# xclock_B.net
KiCad netlist of a schematic drawn in EAGLE
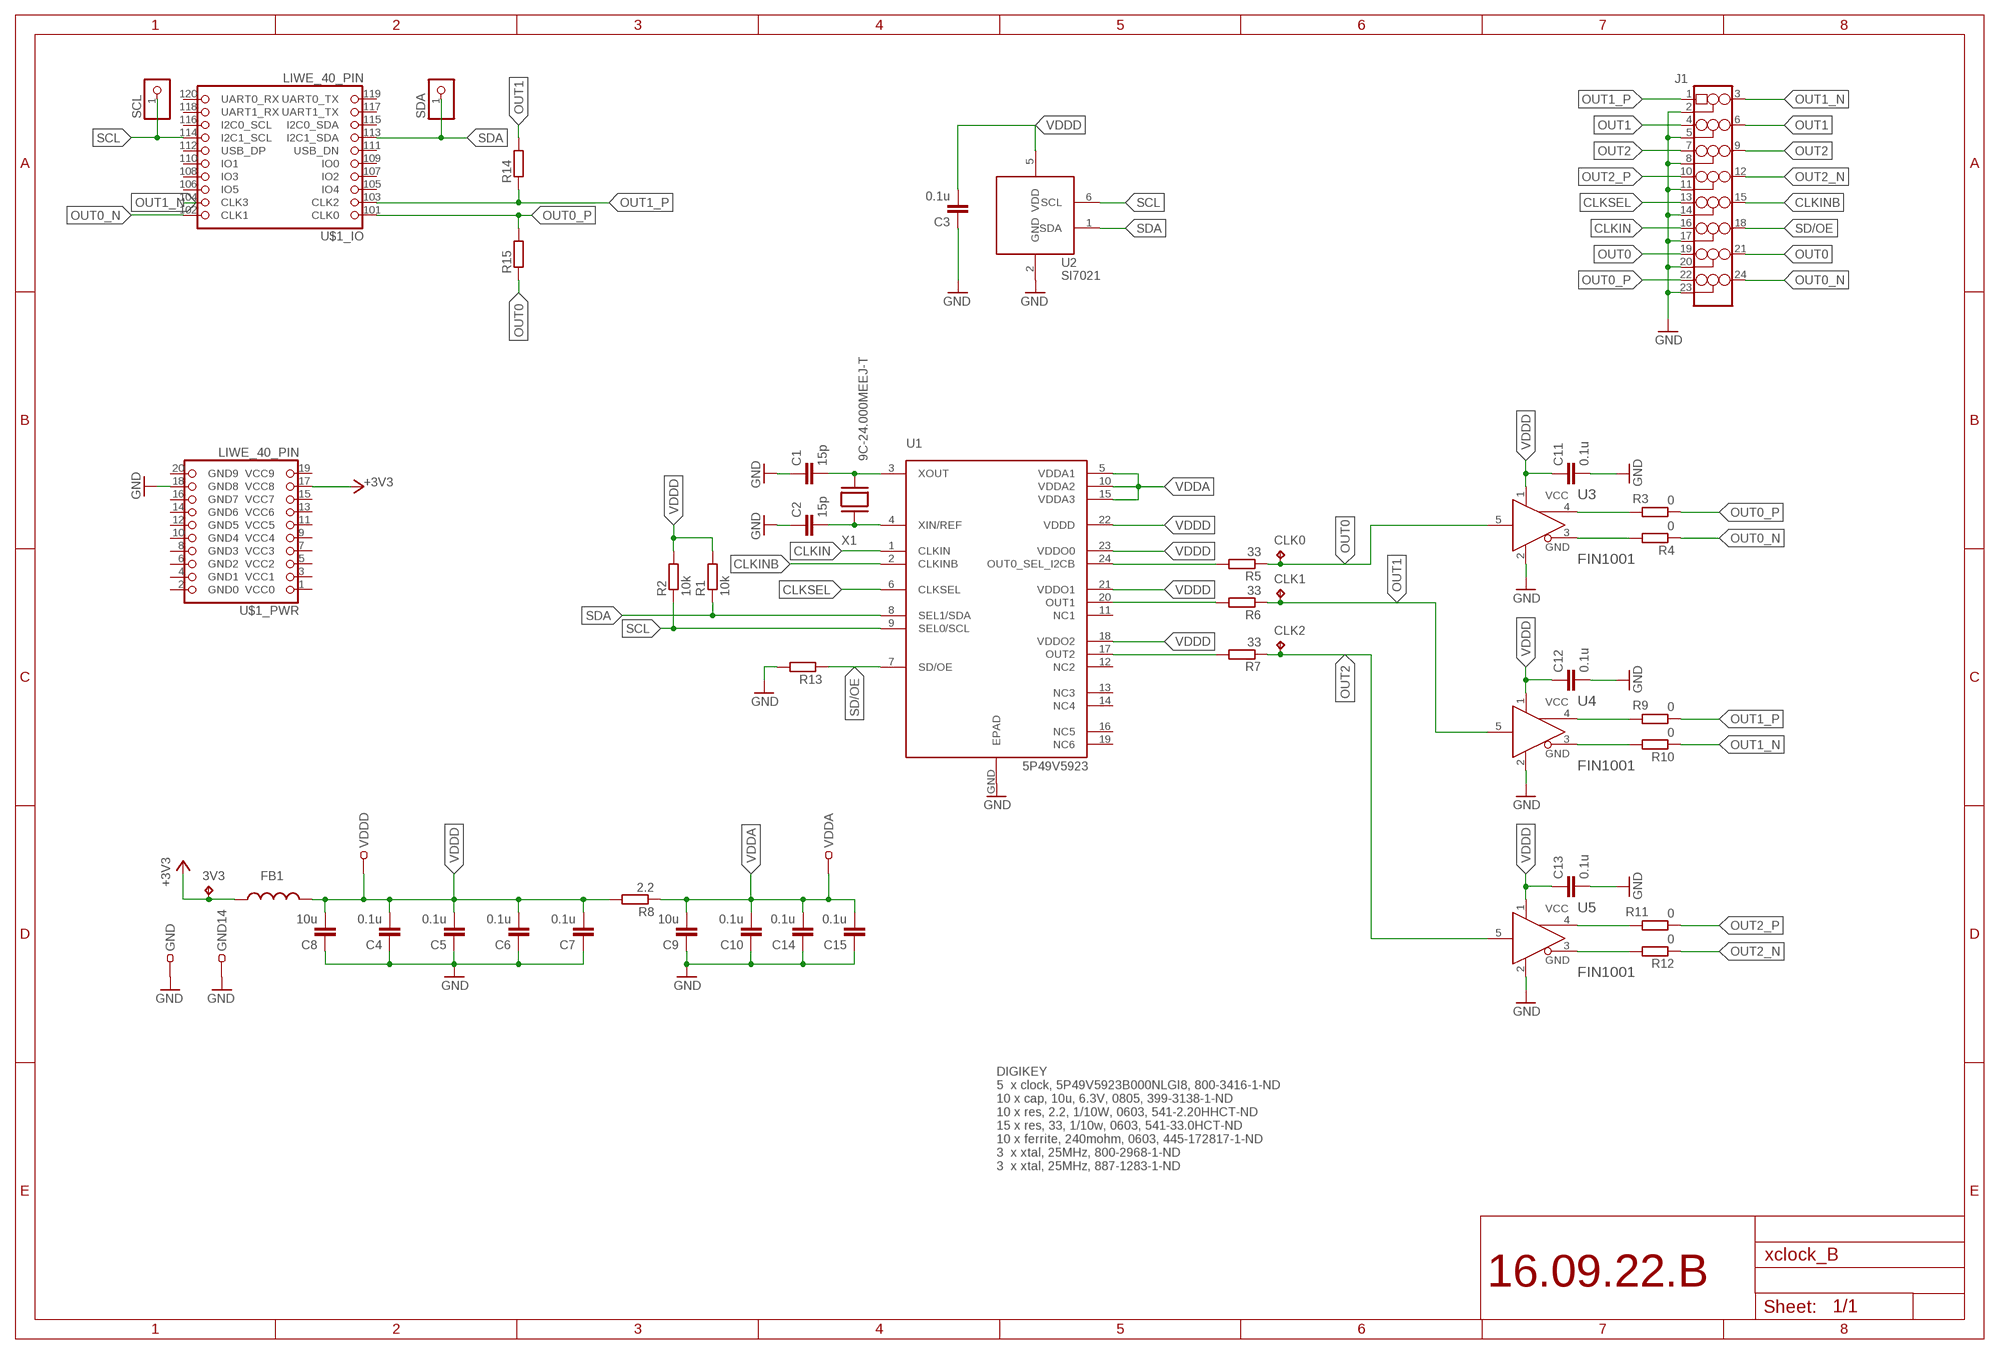
[diagram p0: schematic, sheet 1]

(export (version "E")
  (design (tool "Eeschema 10.0.6"))
  (components
    (comp (ref "3V3")
      (value "TPB1,27")
      (footprint "eagle-import:B1,27")
      (libsource (lib "eagle-import") (part "TPB1,27"))
    )
    (comp (ref "C1")
      (value "15p")
      (footprint "eagle-import:C0603")
      (libsource (lib "eagle-import") (part "C-EUC0603"))
    )
    (comp (ref "C2")
      (value "15p")
      (footprint "eagle-import:C0603")
      (libsource (lib "eagle-import") (part "C-EUC0603"))
    )
    (comp (ref "C3")
      (value "0.1u")
      (footprint "eagle-import:C0603")
      (libsource (lib "eagle-import") (part "C-EUC0603"))
    )
    (comp (ref "C4")
      (value "0.1u")
      (footprint "eagle-import:C0603")
      (libsource (lib "eagle-import") (part "C-EUC0603"))
    )
    (comp (ref "C5")
      (value "0.1u")
      (footprint "eagle-import:C0603")
      (libsource (lib "eagle-import") (part "C-EUC0603"))
    )
    (comp (ref "C6")
      (value "0.1u")
      (footprint "eagle-import:C0603")
      (libsource (lib "eagle-import") (part "C-EUC0603"))
    )
    (comp (ref "C7")
      (value "0.1u")
      (footprint "eagle-import:C0603")
      (libsource (lib "eagle-import") (part "C-EUC0603"))
    )
    (comp (ref "C8")
      (value "10u")
      (footprint "eagle-import:C0805")
      (libsource (lib "eagle-import") (part "C-EUC0805"))
    )
    (comp (ref "C9")
      (value "10u")
      (footprint "eagle-import:C0805")
      (libsource (lib "eagle-import") (part "C-EUC0805"))
    )
    (comp (ref "C10")
      (value "0.1u")
      (footprint "eagle-import:C0603")
      (libsource (lib "eagle-import") (part "C-EUC0603"))
    )
    (comp (ref "C11")
      (value "0.1u")
      (footprint "eagle-import:C0603")
      (libsource (lib "eagle-import") (part "C-EUC0603"))
    )
    (comp (ref "C12")
      (value "0.1u")
      (footprint "eagle-import:C0603")
      (libsource (lib "eagle-import") (part "C-EUC0603"))
    )
    (comp (ref "C13")
      (value "0.1u")
      (footprint "eagle-import:C0603")
      (libsource (lib "eagle-import") (part "C-EUC0603"))
    )
    (comp (ref "C14")
      (value "0.1u")
      (footprint "eagle-import:C0603")
      (libsource (lib "eagle-import") (part "C-EUC0603"))
    )
    (comp (ref "C15")
      (value "0.1u")
      (footprint "eagle-import:C0603")
      (libsource (lib "eagle-import") (part "C-EUC0603"))
    )
    (comp (ref "CLK0")
      (value "TPB1,27")
      (footprint "eagle-import:B1,27")
      (libsource (lib "eagle-import") (part "TPB1,27"))
    )
    (comp (ref "CLK1")
      (value "TPB1,27")
      (footprint "eagle-import:B1,27")
      (libsource (lib "eagle-import") (part "TPB1,27"))
    )
    (comp (ref "CLK2")
      (value "TPB1,27")
      (footprint "eagle-import:B1,27")
      (libsource (lib "eagle-import") (part "TPB1,27"))
    )
    (comp (ref "FB1")
      (value "L0603(1608)")
      (footprint "eagle-import:L0603")
      (libsource (lib "eagle-import") (part "L0603(1608)"))
    )
    (comp (ref "GND")
      (value "TEST-22-MULTICOMP")
      (footprint "eagle-import:TEST_1MM")
      (libsource (lib "eagle-import") (part "TEST-22-MULTICOMP"))
    )
    (comp (ref "GND14")
      (value "TEST-22-MULTICOMP")
      (footprint "eagle-import:TEST_1MM")
      (libsource (lib "eagle-import") (part "TEST-22-MULTICOMP"))
    )
    (comp (ref "J1")
      (value "PINHD-3X8/90")
      (footprint "eagle-import:3X08_90")
      (libsource (lib "eagle-import") (part "PINHD-3X8/90"))
    )
    (comp (ref "R1")
      (value "10k")
      (footprint "eagle-import:R0603")
      (libsource (lib "eagle-import") (part "R-EU_R0603"))
    )
    (comp (ref "R2")
      (value "10k")
      (footprint "eagle-import:R0603")
      (libsource (lib "eagle-import") (part "R-EU_R0603"))
    )
    (comp (ref "R3")
      (value "0")
      (footprint "eagle-import:R0603")
      (libsource (lib "eagle-import") (part "R-EU_R0603"))
    )
    (comp (ref "R4")
      (value "0")
      (footprint "eagle-import:R0603")
      (libsource (lib "eagle-import") (part "R-EU_R0603"))
    )
    (comp (ref "R5")
      (value "33")
      (footprint "eagle-import:R0603")
      (libsource (lib "eagle-import") (part "R-EU_R0603"))
    )
    (comp (ref "R6")
      (value "33")
      (footprint "eagle-import:R0603")
      (libsource (lib "eagle-import") (part "R-EU_R0603"))
    )
    (comp (ref "R7")
      (value "33")
      (footprint "eagle-import:R0603")
      (libsource (lib "eagle-import") (part "R-EU_R0603"))
    )
    (comp (ref "R8")
      (value "2.2")
      (footprint "eagle-import:R0603")
      (libsource (lib "eagle-import") (part "R-EU_R0603"))
    )
    (comp (ref "R9")
      (value "0")
      (footprint "eagle-import:R0603")
      (libsource (lib "eagle-import") (part "R-EU_R0603"))
    )
    (comp (ref "R10")
      (value "0")
      (footprint "eagle-import:R0603")
      (libsource (lib "eagle-import") (part "R-EU_R0603"))
    )
    (comp (ref "R11")
      (value "0")
      (footprint "eagle-import:R0603")
      (libsource (lib "eagle-import") (part "R-EU_R0603"))
    )
    (comp (ref "R12")
      (value "0")
      (footprint "eagle-import:R0603")
      (libsource (lib "eagle-import") (part "R-EU_R0603"))
    )
    (comp (ref "R13")
      (value "R-EU_R0603")
      (footprint "eagle-import:R0603")
      (libsource (lib "eagle-import") (part "R-EU_R0603"))
    )
    (comp (ref "R14")
      (value "R-EU_R0603")
      (footprint "eagle-import:R0603")
      (libsource (lib "eagle-import") (part "R-EU_R0603"))
    )
    (comp (ref "R15")
      (value "R-EU_R0603")
      (footprint "eagle-import:R0603")
      (libsource (lib "eagle-import") (part "R-EU_R0603"))
    )
    (comp (ref "SCL")
      (value "PINHD-1X1")
      (footprint "eagle-import:1X01")
      (libsource (lib "eagle-import") (part "PINHD-1X1"))
    )
    (comp (ref "SDA")
      (value "PINHD-1X1")
      (footprint "eagle-import:1X01")
      (libsource (lib "eagle-import") (part "PINHD-1X1"))
    )
    (comp (ref "U$1")
      (value "LIWE_40_PIN")
      (footprint "eagle-import:LIWE_40_PIN_8X8")
      (libsource (lib "eagle-import") (part "LIWE_40_PIN"))
    )
    (comp (ref "U1")
      (value "5P49V5923")
      (footprint "eagle-import:VFQFPN_24_4X4")
      (libsource (lib "eagle-import") (part "5P49V5923"))
    )
    (comp (ref "U2")
      (value "SI7021")
      (footprint "eagle-import:SI7021")
      (libsource (lib "eagle-import") (part "SI7021"))
    )
    (comp (ref "U3")
      (value "FIN1001")
      (footprint "eagle-import:SOT95P280X140-5N")
      (libsource (lib "eagle-import") (part "FIN1001"))
    )
    (comp (ref "U4")
      (value "FIN1001")
      (footprint "eagle-import:SOT95P280X140-5N")
      (libsource (lib "eagle-import") (part "FIN1001"))
    )
    (comp (ref "U5")
      (value "FIN1001")
      (footprint "eagle-import:SOT95P280X140-5N")
      (libsource (lib "eagle-import") (part "FIN1001"))
    )
    (comp (ref "VDDA")
      (value "TEST-22-MULTICOMP")
      (footprint "eagle-import:TEST_1MM")
      (libsource (lib "eagle-import") (part "TEST-22-MULTICOMP"))
    )
    (comp (ref "VDDD")
      (value "TEST-22-MULTICOMP")
      (footprint "eagle-import:TEST_1MM")
      (libsource (lib "eagle-import") (part "TEST-22-MULTICOMP"))
    )
    (comp (ref "X1")
      (value "9C-24.000MEEJ-T")
      (footprint "eagle-import:TXC_SMD_HC-49S")
      (libsource (lib "eagle-import") (part "TXC_9C"))
    )
  )
  (nets
    (net (code "1") (name "+3V3") (class "Default")
      (node (ref "3V3") (pin "TP") (pinfunction "TP_TP") (pintype "input"))
      (node (ref "FB1") (pin "1") (pinfunction "1_1") (pintype "passive"))
      (node (ref "U$1") (pin "17") (pinfunction "VCC8_17") (pintype "passive"))
    )
    (net (code "2") (name "CLKIN") (class "Default")
      (node (ref "J1") (pin "16") (pinfunction "16_16") (pintype "passive"))
      (node (ref "U1") (pin "1") (pinfunction "CLKIN_1") (pintype "bidirectional"))
    )
    (net (code "3") (name "CLKINB") (class "Default")
      (node (ref "J1") (pin "15") (pinfunction "15_15") (pintype "passive"))
      (node (ref "U1") (pin "2") (pinfunction "CLKINB_2") (pintype "bidirectional"))
    )
    (net (code "4") (name "CLKSEL") (class "Default")
      (node (ref "J1") (pin "13") (pinfunction "13_13") (pintype "passive"))
      (node (ref "U1") (pin "6") (pinfunction "CLKSEL_6") (pintype "bidirectional"))
    )
    (net (code "5") (name "GND") (class "Default")
      (node (ref "C1") (pin "1") (pinfunction "1_1") (pintype "passive"))
      (node (ref "C10") (pin "1") (pinfunction "1_1") (pintype "passive"))
      (node (ref "C11") (pin "2") (pinfunction "2_2") (pintype "passive"))
      (node (ref "C12") (pin "2") (pinfunction "2_2") (pintype "passive"))
      (node (ref "C13") (pin "2") (pinfunction "2_2") (pintype "passive"))
      (node (ref "C14") (pin "1") (pinfunction "1_1") (pintype "passive"))
      (node (ref "C15") (pin "1") (pinfunction "1_1") (pintype "passive"))
      (node (ref "C2") (pin "1") (pinfunction "1_1") (pintype "passive"))
      (node (ref "C3") (pin "1") (pinfunction "1_1") (pintype "passive"))
      (node (ref "C4") (pin "1") (pinfunction "1_1") (pintype "passive"))
      (node (ref "C5") (pin "1") (pinfunction "1_1") (pintype "passive"))
      (node (ref "C6") (pin "1") (pinfunction "1_1") (pintype "passive"))
      (node (ref "C7") (pin "1") (pinfunction "1_1") (pintype "passive"))
      (node (ref "C8") (pin "1") (pinfunction "1_1") (pintype "passive"))
      (node (ref "C9") (pin "1") (pinfunction "1_1") (pintype "passive"))
      (node (ref "GND") (pin "1") (pinfunction "1_1") (pintype "passive"))
      (node (ref "GND14") (pin "1") (pinfunction "1_1") (pintype "passive"))
      (node (ref "J1") (pin "11") (pinfunction "11_11") (pintype "passive"))
      (node (ref "J1") (pin "14") (pinfunction "14_14") (pintype "passive"))
      (node (ref "J1") (pin "17") (pinfunction "17_17") (pintype "passive"))
      (node (ref "J1") (pin "2") (pinfunction "2_2") (pintype "passive"))
      (node (ref "J1") (pin "20") (pinfunction "20_20") (pintype "passive"))
      (node (ref "J1") (pin "23") (pinfunction "23_23") (pintype "passive"))
      (node (ref "J1") (pin "5") (pinfunction "5_5") (pintype "passive"))
      (node (ref "J1") (pin "8") (pinfunction "8_8") (pintype "passive"))
      (node (ref "R13") (pin "2") (pinfunction "2_2") (pintype "passive"))
      (node (ref "U$1") (pin "18") (pinfunction "GND8_18") (pintype "passive"))
      (node (ref "U1") (pin "GND") (pinfunction "EPAD_GND") (pintype "bidirectional"))
      (node (ref "U2") (pin "2") (pinfunction "GND_2") (pintype "power_in"))
      (node (ref "U3") (pin "2") (pinfunction "GND_2") (pintype "passive"))
      (node (ref "U4") (pin "2") (pinfunction "GND_2") (pintype "passive"))
      (node (ref "U5") (pin "2") (pinfunction "GND_2") (pintype "passive"))
    )
    (net (code "6") (name "Net-(U1-OUT0_SEL_I2CB)") (class "Default")
      (node (ref "R5") (pin "2") (pinfunction "2_2") (pintype "passive"))
      (node (ref "U1") (pin "24") (pinfunction "OUT0_SEL_I2CB_24") (pintype "bidirectional"))
    )
    (net (code "7") (name "Net-(U1-OUT1)") (class "Default")
      (node (ref "R6") (pin "2") (pinfunction "2_2") (pintype "passive"))
      (node (ref "U1") (pin "20") (pinfunction "OUT1_20") (pintype "bidirectional"))
    )
    (net (code "8") (name "Net-(U1-OUT2)") (class "Default")
      (node (ref "R7") (pin "2") (pinfunction "2_2") (pintype "passive"))
      (node (ref "U1") (pin "17") (pinfunction "OUT2_17") (pintype "bidirectional"))
    )
    (net (code "9") (name "Net-(U1-XIN{slash}REF)") (class "Default")
      (node (ref "C2") (pin "2") (pinfunction "2_2") (pintype "passive"))
      (node (ref "U1") (pin "4") (pinfunction "XIN/REF_4") (pintype "bidirectional"))
      (node (ref "X1") (pin "1") (pinfunction "1_1") (pintype "passive"))
    )
    (net (code "10") (name "Net-(U1-XOUT)") (class "Default")
      (node (ref "C1") (pin "2") (pinfunction "2_2") (pintype "passive"))
      (node (ref "U1") (pin "3") (pinfunction "XOUT_3") (pintype "bidirectional"))
      (node (ref "X1") (pin "2") (pinfunction "2_2") (pintype "passive"))
    )
    (net (code "11") (name "Net-(U3-ROUT+)") (class "Default")
      (node (ref "R3") (pin "2") (pinfunction "2_2") (pintype "passive"))
      (node (ref "U3") (pin "4") (pinfunction "ROUT+_4") (pintype "output"))
    )
    (net (code "12") (name "Net-(U3-ROUT-)") (class "Default")
      (node (ref "R4") (pin "2") (pinfunction "2_2") (pintype "passive"))
      (node (ref "U3") (pin "3") (pinfunction "ROUT-_3") (pintype "output"))
    )
    (net (code "13") (name "Net-(U4-ROUT+)") (class "Default")
      (node (ref "R9") (pin "2") (pinfunction "2_2") (pintype "passive"))
      (node (ref "U4") (pin "4") (pinfunction "ROUT+_4") (pintype "output"))
    )
    (net (code "14") (name "Net-(U4-ROUT-)") (class "Default")
      (node (ref "R10") (pin "2") (pinfunction "2_2") (pintype "passive"))
      (node (ref "U4") (pin "3") (pinfunction "ROUT-_3") (pintype "output"))
    )
    (net (code "15") (name "Net-(U5-ROUT+)") (class "Default")
      (node (ref "R11") (pin "2") (pinfunction "2_2") (pintype "passive"))
      (node (ref "U5") (pin "4") (pinfunction "ROUT+_4") (pintype "output"))
    )
    (net (code "16") (name "Net-(U5-ROUT-)") (class "Default")
      (node (ref "R12") (pin "2") (pinfunction "2_2") (pintype "passive"))
      (node (ref "U5") (pin "3") (pinfunction "ROUT-_3") (pintype "output"))
    )
    (net (code "17") (name "OUT0") (class "Default")
      (node (ref "CLK0") (pin "TP") (pinfunction "TP_TP") (pintype "input"))
      (node (ref "J1") (pin "19") (pinfunction "19_19") (pintype "passive"))
      (node (ref "J1") (pin "21") (pinfunction "21_21") (pintype "passive"))
      (node (ref "R15") (pin "1") (pinfunction "1_1") (pintype "passive"))
      (node (ref "R5") (pin "1") (pinfunction "1_1") (pintype "passive"))
      (node (ref "U3") (pin "5") (pinfunction "RIN_5") (pintype "input"))
    )
    (net (code "18") (name "OUT0_N") (class "Default")
      (node (ref "J1") (pin "24") (pinfunction "24_24") (pintype "passive"))
      (node (ref "R4") (pin "1") (pinfunction "1_1") (pintype "passive"))
      (node (ref "U$1") (pin "102") (pinfunction "CLK1_102") (pintype "passive"))
    )
    (net (code "19") (name "OUT0_P") (class "Default")
      (node (ref "J1") (pin "22") (pinfunction "22_22") (pintype "passive"))
      (node (ref "R15") (pin "2") (pinfunction "2_2") (pintype "passive"))
      (node (ref "R3") (pin "1") (pinfunction "1_1") (pintype "passive"))
      (node (ref "U$1") (pin "101") (pinfunction "CLK0_101") (pintype "passive"))
    )
    (net (code "20") (name "OUT1") (class "Default")
      (node (ref "CLK1") (pin "TP") (pinfunction "TP_TP") (pintype "input"))
      (node (ref "J1") (pin "4") (pinfunction "4_4") (pintype "passive"))
      (node (ref "J1") (pin "6") (pinfunction "6_6") (pintype "passive"))
      (node (ref "R14") (pin "2") (pinfunction "2_2") (pintype "passive"))
      (node (ref "R6") (pin "1") (pinfunction "1_1") (pintype "passive"))
      (node (ref "U4") (pin "5") (pinfunction "RIN_5") (pintype "input"))
    )
    (net (code "21") (name "OUT1_N") (class "Default")
      (node (ref "J1") (pin "3") (pinfunction "3_3") (pintype "passive"))
      (node (ref "R10") (pin "1") (pinfunction "1_1") (pintype "passive"))
      (node (ref "U$1") (pin "104") (pinfunction "CLK3_104") (pintype "passive"))
    )
    (net (code "22") (name "OUT1_P") (class "Default")
      (node (ref "J1") (pin "1") (pinfunction "1_1") (pintype "passive"))
      (node (ref "R14") (pin "1") (pinfunction "1_1") (pintype "passive"))
      (node (ref "R9") (pin "1") (pinfunction "1_1") (pintype "passive"))
      (node (ref "U$1") (pin "103") (pinfunction "CLK2_103") (pintype "passive"))
    )
    (net (code "23") (name "OUT2") (class "Default")
      (node (ref "CLK2") (pin "TP") (pinfunction "TP_TP") (pintype "input"))
      (node (ref "J1") (pin "7") (pinfunction "7_7") (pintype "passive"))
      (node (ref "J1") (pin "9") (pinfunction "9_9") (pintype "passive"))
      (node (ref "R7") (pin "1") (pinfunction "1_1") (pintype "passive"))
      (node (ref "U5") (pin "5") (pinfunction "RIN_5") (pintype "input"))
    )
    (net (code "24") (name "OUT2_N") (class "Default")
      (node (ref "J1") (pin "12") (pinfunction "12_12") (pintype "passive"))
      (node (ref "R12") (pin "1") (pinfunction "1_1") (pintype "passive"))
    )
    (net (code "25") (name "OUT2_P") (class "Default")
      (node (ref "J1") (pin "10") (pinfunction "10_10") (pintype "passive"))
      (node (ref "R11") (pin "1") (pinfunction "1_1") (pintype "passive"))
    )
    (net (code "26") (name "SCL") (class "Default")
      (node (ref "R2") (pin "1") (pinfunction "1_1") (pintype "passive"))
      (node (ref "SCL") (pin "1") (pinfunction "1_1") (pintype "passive"))
      (node (ref "U$1") (pin "114") (pinfunction "I2C1_SCL_114") (pintype "passive"))
      (node (ref "U1") (pin "9") (pinfunction "SEL0/SCL_9") (pintype "bidirectional"))
      (node (ref "U2") (pin "6") (pinfunction "SCL_6") (pintype "bidirectional"))
    )
    (net (code "27") (name "SDA") (class "Default")
      (node (ref "R1") (pin "1") (pinfunction "1_1") (pintype "passive"))
      (node (ref "SDA") (pin "1") (pinfunction "1_1") (pintype "passive"))
      (node (ref "U$1") (pin "113") (pinfunction "I2C1_SDA_113") (pintype "passive"))
      (node (ref "U1") (pin "8") (pinfunction "SEL1/SDA_8") (pintype "bidirectional"))
      (node (ref "U2") (pin "1") (pinfunction "SDA_1") (pintype "bidirectional"))
    )
    (net (code "28") (name "SD{slash}OE") (class "Default")
      (node (ref "J1") (pin "18") (pinfunction "18_18") (pintype "passive"))
      (node (ref "R13") (pin "1") (pinfunction "1_1") (pintype "passive"))
      (node (ref "U1") (pin "7") (pinfunction "SD/OE_7") (pintype "bidirectional"))
    )
    (net (code "29") (name "VDDA") (class "Default")
      (node (ref "C10") (pin "2") (pinfunction "2_2") (pintype "passive"))
      (node (ref "C14") (pin "2") (pinfunction "2_2") (pintype "passive"))
      (node (ref "C15") (pin "2") (pinfunction "2_2") (pintype "passive"))
      (node (ref "C9") (pin "2") (pinfunction "2_2") (pintype "passive"))
      (node (ref "R8") (pin "1") (pinfunction "1_1") (pintype "passive"))
      (node (ref "U1") (pin "10") (pinfunction "VDDA2_10") (pintype "bidirectional"))
      (node (ref "U1") (pin "15") (pinfunction "VDDA3_15") (pintype "bidirectional"))
      (node (ref "U1") (pin "5") (pinfunction "VDDA1_5") (pintype "bidirectional"))
      (node (ref "VDDA") (pin "1") (pinfunction "1_1") (pintype "passive"))
    )
    (net (code "30") (name "VDDD") (class "Default")
      (node (ref "C11") (pin "1") (pinfunction "1_1") (pintype "passive"))
      (node (ref "C12") (pin "1") (pinfunction "1_1") (pintype "passive"))
      (node (ref "C13") (pin "1") (pinfunction "1_1") (pintype "passive"))
      (node (ref "C3") (pin "2") (pinfunction "2_2") (pintype "passive"))
      (node (ref "C4") (pin "2") (pinfunction "2_2") (pintype "passive"))
      (node (ref "C5") (pin "2") (pinfunction "2_2") (pintype "passive"))
      (node (ref "C6") (pin "2") (pinfunction "2_2") (pintype "passive"))
      (node (ref "C7") (pin "2") (pinfunction "2_2") (pintype "passive"))
      (node (ref "C8") (pin "2") (pinfunction "2_2") (pintype "passive"))
      (node (ref "FB1") (pin "2") (pinfunction "2_2") (pintype "passive"))
      (node (ref "R1") (pin "2") (pinfunction "2_2") (pintype "passive"))
      (node (ref "R2") (pin "2") (pinfunction "2_2") (pintype "passive"))
      (node (ref "R8") (pin "2") (pinfunction "2_2") (pintype "passive"))
      (node (ref "U1") (pin "18") (pinfunction "VDDO2_18") (pintype "bidirectional"))
      (node (ref "U1") (pin "21") (pinfunction "VDDO1_21") (pintype "bidirectional"))
      (node (ref "U1") (pin "22") (pinfunction "VDDD_22") (pintype "bidirectional"))
      (node (ref "U1") (pin "23") (pinfunction "VDDO0_23") (pintype "bidirectional"))
      (node (ref "U2") (pin "5") (pinfunction "VDD_5") (pintype "power_in"))
      (node (ref "U3") (pin "1") (pinfunction "VCC_1") (pintype "power_in"))
      (node (ref "U4") (pin "1") (pinfunction "VCC_1") (pintype "power_in"))
      (node (ref "U5") (pin "1") (pinfunction "VCC_1") (pintype "power_in"))
      (node (ref "VDDD") (pin "1") (pinfunction "1_1") (pintype "passive"))
    )
    (net (code "31") (name "unconnected-(U$1A-I2C0_SCL-Pad116)") (class "Default")
      (node (ref "U$1") (pin "116") (pinfunction "I2C0_SCL_116") (pintype "passive"))
    )
    (net (code "32") (name "unconnected-(U$1A-I2C0_SDA-Pad115)") (class "Default")
      (node (ref "U$1") (pin "115") (pinfunction "I2C0_SDA_115") (pintype "passive"))
    )
    (net (code "33") (name "unconnected-(U$1A-IO0-Pad109)") (class "Default")
      (node (ref "U$1") (pin "109") (pinfunction "IO0_109") (pintype "passive"))
    )
    (net (code "34") (name "unconnected-(U$1A-IO1-Pad110)") (class "Default")
      (node (ref "U$1") (pin "110") (pinfunction "IO1_110") (pintype "passive"))
    )
    (net (code "35") (name "unconnected-(U$1A-IO2-Pad107)") (class "Default")
      (node (ref "U$1") (pin "107") (pinfunction "IO2_107") (pintype "passive"))
    )
    (net (code "36") (name "unconnected-(U$1A-IO3-Pad108)") (class "Default")
      (node (ref "U$1") (pin "108") (pinfunction "IO3_108") (pintype "passive"))
    )
    (net (code "37") (name "unconnected-(U$1A-IO4-Pad105)") (class "Default")
      (node (ref "U$1") (pin "105") (pinfunction "IO4_105") (pintype "passive"))
    )
    (net (code "38") (name "unconnected-(U$1A-IO5-Pad106)") (class "Default")
      (node (ref "U$1") (pin "106") (pinfunction "IO5_106") (pintype "passive"))
    )
    (net (code "39") (name "unconnected-(U$1A-UART0_RX-Pad120)") (class "Default")
      (node (ref "U$1") (pin "120") (pinfunction "UART0_RX_120") (pintype "passive"))
    )
    (net (code "40") (name "unconnected-(U$1A-UART0_TX-Pad119)") (class "Default")
      (node (ref "U$1") (pin "119") (pinfunction "UART0_TX_119") (pintype "passive"))
    )
    (net (code "41") (name "unconnected-(U$1A-UART1_RX-Pad118)") (class "Default")
      (node (ref "U$1") (pin "118") (pinfunction "UART1_RX_118") (pintype "passive"))
    )
    (net (code "42") (name "unconnected-(U$1A-UART1_TX-Pad117)") (class "Default")
      (node (ref "U$1") (pin "117") (pinfunction "UART1_TX_117") (pintype "passive"))
    )
    (net (code "43") (name "unconnected-(U$1A-USB_DN-Pad111)") (class "Default")
      (node (ref "U$1") (pin "111") (pinfunction "USB_DN_111") (pintype "passive"))
    )
    (net (code "44") (name "unconnected-(U$1A-USB_DP-Pad112)") (class "Default")
      (node (ref "U$1") (pin "112") (pinfunction "USB_DP_112") (pintype "passive"))
    )
    (net (code "45") (name "unconnected-(U$1B-GND0-Pad2)") (class "Default")
      (node (ref "U$1") (pin "2") (pinfunction "GND0_2") (pintype "passive"))
    )
    (net (code "46") (name "unconnected-(U$1B-GND1-Pad4)") (class "Default")
      (node (ref "U$1") (pin "4") (pinfunction "GND1_4") (pintype "passive"))
    )
    (net (code "47") (name "unconnected-(U$1B-GND2-Pad6)") (class "Default")
      (node (ref "U$1") (pin "6") (pinfunction "GND2_6") (pintype "passive"))
    )
    (net (code "48") (name "unconnected-(U$1B-GND3-Pad8)") (class "Default")
      (node (ref "U$1") (pin "8") (pinfunction "GND3_8") (pintype "passive"))
    )
    (net (code "49") (name "unconnected-(U$1B-GND4-Pad10)") (class "Default")
      (node (ref "U$1") (pin "10") (pinfunction "GND4_10") (pintype "passive"))
    )
    (net (code "50") (name "unconnected-(U$1B-GND5-Pad12)") (class "Default")
      (node (ref "U$1") (pin "12") (pinfunction "GND5_12") (pintype "passive"))
    )
    (net (code "51") (name "unconnected-(U$1B-GND6-Pad14)") (class "Default")
      (node (ref "U$1") (pin "14") (pinfunction "GND6_14") (pintype "passive"))
    )
    (net (code "52") (name "unconnected-(U$1B-GND7-Pad16)") (class "Default")
      (node (ref "U$1") (pin "16") (pinfunction "GND7_16") (pintype "passive"))
    )
    (net (code "53") (name "unconnected-(U$1B-GND9-Pad20)") (class "Default")
      (node (ref "U$1") (pin "20") (pinfunction "GND9_20") (pintype "passive"))
    )
    (net (code "54") (name "unconnected-(U$1B-VCC0-Pad1)") (class "Default")
      (node (ref "U$1") (pin "1") (pinfunction "VCC0_1") (pintype "passive"))
    )
    (net (code "55") (name "unconnected-(U$1B-VCC1-Pad3)") (class "Default")
      (node (ref "U$1") (pin "3") (pinfunction "VCC1_3") (pintype "passive"))
    )
    (net (code "56") (name "unconnected-(U$1B-VCC2-Pad5)") (class "Default")
      (node (ref "U$1") (pin "5") (pinfunction "VCC2_5") (pintype "passive"))
    )
    (net (code "57") (name "unconnected-(U$1B-VCC3-Pad7)") (class "Default")
      (node (ref "U$1") (pin "7") (pinfunction "VCC3_7") (pintype "passive"))
    )
    (net (code "58") (name "unconnected-(U$1B-VCC4-Pad9)") (class "Default")
      (node (ref "U$1") (pin "9") (pinfunction "VCC4_9") (pintype "passive"))
    )
    (net (code "59") (name "unconnected-(U$1B-VCC5-Pad11)") (class "Default")
      (node (ref "U$1") (pin "11") (pinfunction "VCC5_11") (pintype "passive"))
    )
    (net (code "60") (name "unconnected-(U$1B-VCC6-Pad13)") (class "Default")
      (node (ref "U$1") (pin "13") (pinfunction "VCC6_13") (pintype "passive"))
    )
    (net (code "61") (name "unconnected-(U$1B-VCC7-Pad15)") (class "Default")
      (node (ref "U$1") (pin "15") (pinfunction "VCC7_15") (pintype "passive"))
    )
    (net (code "62") (name "unconnected-(U$1B-VCC9-Pad19)") (class "Default")
      (node (ref "U$1") (pin "19") (pinfunction "VCC9_19") (pintype "passive"))
    )
    (net (code "63") (name "unconnected-(U1-NC1-Pad11)") (class "Default")
      (node (ref "U1") (pin "11") (pinfunction "NC1_11") (pintype "bidirectional"))
    )
    (net (code "64") (name "unconnected-(U1-NC2-Pad12)") (class "Default")
      (node (ref "U1") (pin "12") (pinfunction "NC2_12") (pintype "bidirectional"))
    )
    (net (code "65") (name "unconnected-(U1-NC3-Pad13)") (class "Default")
      (node (ref "U1") (pin "13") (pinfunction "NC3_13") (pintype "bidirectional"))
    )
    (net (code "66") (name "unconnected-(U1-NC4-Pad14)") (class "Default")
      (node (ref "U1") (pin "14") (pinfunction "NC4_14") (pintype "bidirectional"))
    )
    (net (code "67") (name "unconnected-(U1-NC5-Pad16)") (class "Default")
      (node (ref "U1") (pin "16") (pinfunction "NC5_16") (pintype "bidirectional"))
    )
    (net (code "68") (name "unconnected-(U1-NC6-Pad19)") (class "Default")
      (node (ref "U1") (pin "19") (pinfunction "NC6_19") (pintype "bidirectional"))
    )
  )
)
